# design.net
KiCad netlist of a schematic drawn in Altium Designer
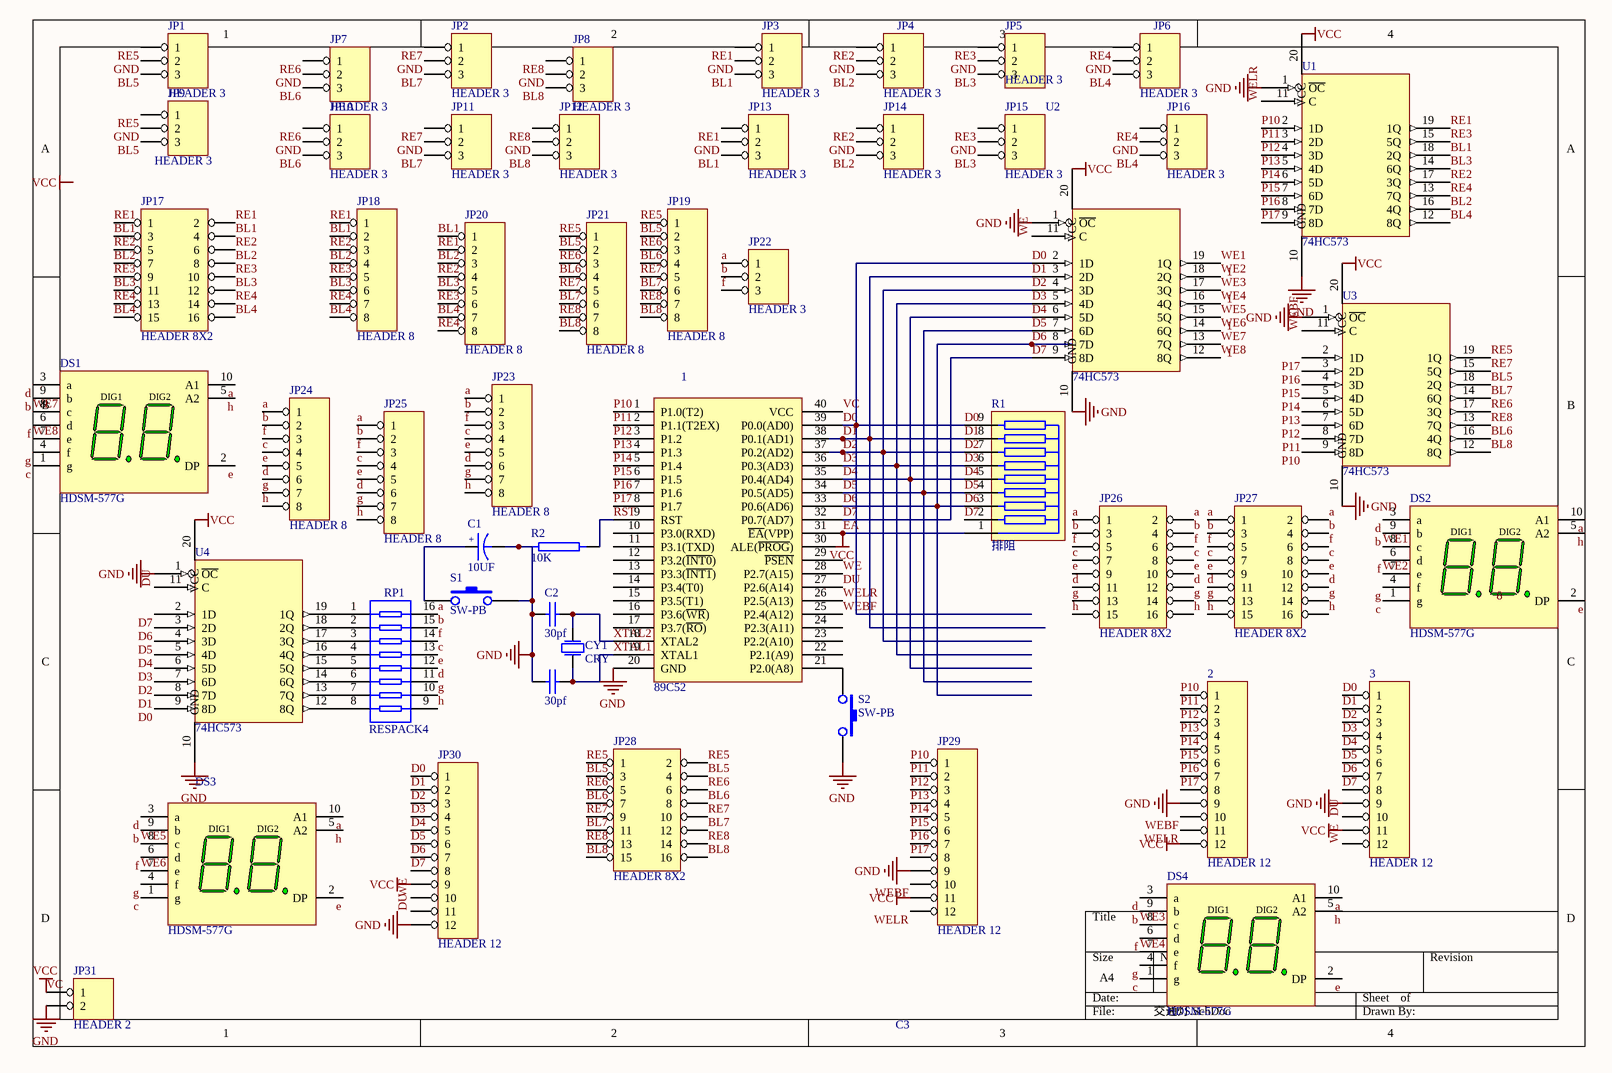
[diagram p0: 交通灯.SchDoc]

(export (version "E")
  (design (tool "Eeschema 10.0.6"))
  (components
    (comp (ref "1") (value "89C52") (footprint "DIP-40") (libsource (lib "51单片机") (part "89C52")))
    (comp (ref "2")
      (value "HEADER 12")
      (footprint "HDR1X12")
      (description "12 Pin Header")
      (libsource (lib "杂元件库") (part "HEADER 12"))
    )
    (comp (ref "3")
      (value "HEADER 12")
      (footprint "HDR1X12")
      (description "12 Pin Header")
      (libsource (lib "杂元件库") (part "HEADER 12"))
    )
    (comp (ref "C1")
      (value "10UF")
      (footprint "3216C")
      (description "钽电容")
      (libsource (lib "常用器件") (part "CAP-T"))
    )
    (comp (ref "C2") (value "30pf") (footprint "RAD0.1") (libsource (lib "C电容") (part "CAP1")))
    (comp (ref "C3") (value "30pf") (footprint "RAD0.1") (libsource (lib "C电容") (part "CAP1")))
    (comp (ref "CY1") (value "CRY") (footprint "XTAL-1") (libsource (lib "CRY晶振") (part "CRY")))
    (comp (ref "DS1")
      (value "HDSM-577G")
      (footprint "HDSM-577")
      (description "9.2 mm Green 7-Segment Display: 2-Digit, RH DP")
      (fields (field (name "PUBLISHER") "Altium Limited"))
      (libsource (lib "Avago LED Display 7-Segment, 2-Digit") (part "HDSM-577G"))
    )
    (comp (ref "DS2")
      (value "HDSM-577G")
      (footprint "HDSM-577")
      (description "9.2 mm Green 7-Segment Display: 2-Digit, RH DP")
      (fields (field (name "PUBLISHER") "Altium Limited"))
      (libsource (lib "Avago LED Display 7-Segment, 2-Digit") (part "HDSM-577G"))
    )
    (comp (ref "DS3")
      (value "HDSM-577G")
      (footprint "HDSM-577")
      (description "9.2 mm Green 7-Segment Display: 2-Digit, RH DP")
      (fields (field (name "PUBLISHER") "Altium Limited"))
      (libsource (lib "Avago LED Display 7-Segment, 2-Digit") (part "HDSM-577G"))
    )
    (comp (ref "DS4")
      (value "HDSM-577G")
      (footprint "HDSM-577")
      (description "9.2 mm Green 7-Segment Display: 2-Digit, RH DP")
      (fields (field (name "PUBLISHER") "Altium Limited"))
      (libsource (lib "Avago LED Display 7-Segment, 2-Digit") (part "HDSM-577G"))
    )
    (comp (ref "JP1")
      (value "HEADER 3")
      (footprint "Header3 80mil")
      (libsource (lib "杂元件库") (part "HEADER 3"))
    )
    (comp (ref "JP2")
      (value "HEADER 3")
      (footprint "Header3 80mil")
      (libsource (lib "杂元件库") (part "HEADER 3"))
    )
    (comp (ref "JP3")
      (value "HEADER 3")
      (footprint "Header3 80mil")
      (libsource (lib "杂元件库") (part "HEADER 3"))
    )
    (comp (ref "JP4")
      (value "HEADER 3")
      (footprint "Header3 80mil")
      (libsource (lib "杂元件库") (part "HEADER 3"))
    )
    (comp (ref "JP5")
      (value "HEADER 3")
      (footprint "Header3 80mil")
      (libsource (lib "杂元件库") (part "HEADER 3"))
    )
    (comp (ref "JP6")
      (value "HEADER 3")
      (footprint "Header3 80mil")
      (libsource (lib "杂元件库") (part "HEADER 3"))
    )
    (comp (ref "JP7")
      (value "HEADER 3")
      (footprint "Header3 80mil")
      (libsource (lib "杂元件库") (part "HEADER 3"))
    )
    (comp (ref "JP8")
      (value "HEADER 3")
      (footprint "Header3 80mil")
      (libsource (lib "杂元件库") (part "HEADER 3"))
    )
    (comp (ref "JP9")
      (value "HEADER 3")
      (footprint "Header3 80mil")
      (libsource (lib "杂元件库") (part "HEADER 3"))
    )
    (comp (ref "JP10")
      (value "HEADER 3")
      (footprint "Header3 80mil")
      (libsource (lib "杂元件库") (part "HEADER 3"))
    )
    (comp (ref "JP11")
      (value "HEADER 3")
      (footprint "Header3 80mil")
      (libsource (lib "杂元件库") (part "HEADER 3"))
    )
    (comp (ref "JP12")
      (value "HEADER 3")
      (footprint "Header3 80mil")
      (libsource (lib "杂元件库") (part "HEADER 3"))
    )
    (comp (ref "JP13")
      (value "HEADER 3")
      (footprint "Header3 80mil")
      (libsource (lib "杂元件库") (part "HEADER 3"))
    )
    (comp (ref "JP14")
      (value "HEADER 3")
      (footprint "Header3 80mil")
      (libsource (lib "杂元件库") (part "HEADER 3"))
    )
    (comp (ref "JP15")
      (value "HEADER 3")
      (footprint "Header3 80mil")
      (libsource (lib "杂元件库") (part "HEADER 3"))
    )
    (comp (ref "JP16")
      (value "HEADER 3")
      (footprint "Header3 80mil")
      (libsource (lib "杂元件库") (part "HEADER 3"))
    )
    (comp (ref "JP17") (value "HEADER 8X2") (footprint "HDR2X8") (libsource (lib "杂元件库") (part "HEADER 8X2")))
    (comp (ref "JP18")
      (value "HEADER 8")
      (footprint "HDR1X8")
      (description "8 Pin Header")
      (libsource (lib "杂元件库") (part "HEADER 8"))
    )
    (comp (ref "JP19")
      (value "HEADER 8")
      (footprint "HDR1X8")
      (description "8 Pin Header")
      (libsource (lib "杂元件库") (part "HEADER 8"))
    )
    (comp (ref "JP20")
      (value "HEADER 8")
      (footprint "HDR1X8")
      (description "8 Pin Header")
      (libsource (lib "杂元件库") (part "HEADER 8"))
    )
    (comp (ref "JP21")
      (value "HEADER 8")
      (footprint "HDR1X8")
      (description "8 Pin Header")
      (libsource (lib "杂元件库") (part "HEADER 8"))
    )
    (comp (ref "JP22")
      (value "HEADER 3")
      (footprint "Header3 80mil")
      (libsource (lib "杂元件库") (part "HEADER 3"))
    )
    (comp (ref "JP23")
      (value "HEADER 8")
      (footprint "HDR1X8")
      (description "8 Pin Header")
      (libsource (lib "杂元件库") (part "HEADER 8"))
    )
    (comp (ref "JP24")
      (value "HEADER 8")
      (footprint "HDR1X8")
      (description "8 Pin Header")
      (libsource (lib "杂元件库") (part "HEADER 8"))
    )
    (comp (ref "JP25")
      (value "HEADER 8")
      (footprint "HDR1X8")
      (description "8 Pin Header")
      (libsource (lib "杂元件库") (part "HEADER 8"))
    )
    (comp (ref "JP26") (value "HEADER 8X2") (footprint "HDR2X8") (libsource (lib "杂元件库") (part "HEADER 8X2")))
    (comp (ref "JP27") (value "HEADER 8X2") (footprint "HDR2X8") (libsource (lib "杂元件库") (part "HEADER 8X2")))
    (comp (ref "JP28") (value "HEADER 8X2") (footprint "HDR2X8") (libsource (lib "杂元件库") (part "HEADER 8X2")))
    (comp (ref "JP29")
      (value "HEADER 12")
      (footprint "HDR1X12")
      (description "12 Pin Header")
      (libsource (lib "杂元件库") (part "HEADER 12"))
    )
    (comp (ref "JP30")
      (value "HEADER 12")
      (footprint "HDR1X12")
      (description "12 Pin Header")
      (libsource (lib "杂元件库") (part "HEADER 12"))
    )
    (comp (ref "JP31") (value "HEADER 2") (footprint "HDR1X2") (libsource (lib "杂元件库") (part "HEADER 2")))
    (comp (ref "R1") (value "排阻") (footprint "sip9") (libsource (lib "R电阻") (part "排阻")))
    (comp (ref "R2") (value "10K") (footprint "AXIAL0.5") (libsource (lib "电阻(1)") (part "RES")))
    (comp (ref "RP1") (value "RESPACK4") (footprint "DIP16") (libsource (lib "电阻") (part "RESPACK4")))
    (comp (ref "S1") (value "SW-PB") (footprint "SWITCH") (libsource (lib "SW开关") (part "SW-PB")))
    (comp (ref "S2") (value "SW-PB") (footprint "SWITCH") (libsource (lib "SW开关") (part "SW-PB")))
    (comp (ref "U1") (value "74HC573") (footprint "DIP-20") (libsource (lib "74xxTTL") (part "74HC573")))
    (comp (ref "U2") (value "74HC573") (footprint "DIP-20") (libsource (lib "") (part "74HC573_1")))
    (comp (ref "U3") (value "74HC573") (footprint "DIP-20") (libsource (lib "74xxTTL") (part "74HC573")))
    (comp (ref "U4") (value "74HC573") (footprint "DIP-20") (libsource (lib "") (part "74HC573_1")))
  )
  (nets
    (net (code "3") (name "/BL1") (class "Default")
      (node (ref "JP13") (pin "3") (pinfunction "3_3") (pintype "passive"))
      (node (ref "JP17") (pin "3") (pinfunction "3_3") (pintype "passive"))
      (node (ref "JP17") (pin "4") (pinfunction "4_4") (pintype "passive"))
      (node (ref "JP18") (pin "2") (pinfunction "2_2") (pintype "passive"))
      (node (ref "JP20") (pin "1") (pinfunction "1_1") (pintype "passive"))
      (node (ref "JP3") (pin "3") (pinfunction "3_3") (pintype "passive"))
      (node (ref "U1") (pin "18") (pinfunction "2Q_18") (pintype "output"))
    )
    (net (code "4") (name "/BL2") (class "Default")
      (node (ref "JP14") (pin "3") (pinfunction "3_3") (pintype "passive"))
      (node (ref "JP17") (pin "7") (pinfunction "7_7") (pintype "passive"))
      (node (ref "JP17") (pin "8") (pinfunction "8_8") (pintype "passive"))
      (node (ref "JP18") (pin "4") (pinfunction "4_4") (pintype "passive"))
      (node (ref "JP20") (pin "3") (pinfunction "3_3") (pintype "passive"))
      (node (ref "JP4") (pin "3") (pinfunction "3_3") (pintype "passive"))
      (node (ref "U1") (pin "16") (pinfunction "4Q_16") (pintype "output"))
    )
    (net (code "5") (name "/BL3") (class "Default")
      (node (ref "JP15") (pin "3") (pinfunction "3_3") (pintype "passive"))
      (node (ref "JP17") (pin "11") (pinfunction "11_11") (pintype "passive"))
      (node (ref "JP17") (pin "12") (pinfunction "12_12") (pintype "passive"))
      (node (ref "JP18") (pin "6") (pinfunction "6_6") (pintype "passive"))
      (node (ref "JP20") (pin "5") (pinfunction "5_5") (pintype "passive"))
      (node (ref "JP5") (pin "3") (pinfunction "3_3") (pintype "passive"))
      (node (ref "U1") (pin "14") (pinfunction "6Q_14") (pintype "output"))
    )
    (net (code "6") (name "/BL4") (class "Default")
      (node (ref "JP16") (pin "3") (pinfunction "3_3") (pintype "passive"))
      (node (ref "JP17") (pin "15") (pinfunction "15_15") (pintype "passive"))
      (node (ref "JP17") (pin "16") (pinfunction "16_16") (pintype "passive"))
      (node (ref "JP18") (pin "8") (pinfunction "8_8") (pintype "passive"))
      (node (ref "JP20") (pin "7") (pinfunction "7_7") (pintype "passive"))
      (node (ref "JP6") (pin "3") (pinfunction "3_3") (pintype "passive"))
      (node (ref "U1") (pin "12") (pinfunction "8Q_12") (pintype "output"))
    )
    (net (code "7") (name "/BL5") (class "Default")
      (node (ref "JP1") (pin "3") (pinfunction "3_3") (pintype "passive"))
      (node (ref "JP19") (pin "2") (pinfunction "2_2") (pintype "passive"))
      (node (ref "JP21") (pin "2") (pinfunction "2_2") (pintype "passive"))
      (node (ref "JP28") (pin "3") (pinfunction "3_3") (pintype "passive"))
      (node (ref "JP28") (pin "4") (pinfunction "4_4") (pintype "passive"))
      (node (ref "JP9") (pin "3") (pinfunction "3_3") (pintype "passive"))
      (node (ref "U3") (pin "18") (pinfunction "2Q_18") (pintype "output"))
    )
    (net (code "8") (name "/BL6") (class "Default")
      (node (ref "JP10") (pin "3") (pinfunction "3_3") (pintype "passive"))
      (node (ref "JP19") (pin "4") (pinfunction "4_4") (pintype "passive"))
      (node (ref "JP21") (pin "4") (pinfunction "4_4") (pintype "passive"))
      (node (ref "JP28") (pin "7") (pinfunction "7_7") (pintype "passive"))
      (node (ref "JP28") (pin "8") (pinfunction "8_8") (pintype "passive"))
      (node (ref "JP7") (pin "3") (pinfunction "3_3") (pintype "passive"))
      (node (ref "U3") (pin "16") (pinfunction "4Q_16") (pintype "output"))
    )
    (net (code "9") (name "/BL7") (class "Default")
      (node (ref "JP11") (pin "3") (pinfunction "3_3") (pintype "passive"))
      (node (ref "JP19") (pin "6") (pinfunction "6_6") (pintype "passive"))
      (node (ref "JP2") (pin "3") (pinfunction "3_3") (pintype "passive"))
      (node (ref "JP21") (pin "6") (pinfunction "6_6") (pintype "passive"))
      (node (ref "JP28") (pin "11") (pinfunction "11_11") (pintype "passive"))
      (node (ref "JP28") (pin "12") (pinfunction "12_12") (pintype "passive"))
      (node (ref "U3") (pin "14") (pinfunction "6Q_14") (pintype "output"))
    )
    (net (code "10") (name "/BL8") (class "Default")
      (node (ref "JP12") (pin "3") (pinfunction "3_3") (pintype "passive"))
      (node (ref "JP19") (pin "8") (pinfunction "8_8") (pintype "passive"))
      (node (ref "JP21") (pin "8") (pinfunction "8_8") (pintype "passive"))
      (node (ref "JP28") (pin "15") (pinfunction "15_15") (pintype "passive"))
      (node (ref "JP28") (pin "16") (pinfunction "16_16") (pintype "passive"))
      (node (ref "JP8") (pin "3") (pinfunction "3_3") (pintype "passive"))
      (node (ref "U3") (pin "12") (pinfunction "8Q_12") (pintype "output"))
    )
    (net (code "11") (name "/D0") (class "Default")
      (node (ref "1") (pin "39") (pinfunction "P0.0(AD0)_39") (pintype "passive"))
      (node (ref "3") (pin "1") (pinfunction "1_1") (pintype "passive"))
      (node (ref "JP30") (pin "1") (pinfunction "1_1") (pintype "passive"))
      (node (ref "R1") (pin "9") (pinfunction "9_9") (pintype "passive"))
      (node (ref "U2") (pin "2") (pinfunction "1D_2") (pintype "input"))
      (node (ref "U4") (pin "9") (pinfunction "8D_9") (pintype "input"))
    )
    (net (code "12") (name "/D1") (class "Default")
      (node (ref "1") (pin "38") (pinfunction "P0.1(AD1)_38") (pintype "passive"))
      (node (ref "3") (pin "2") (pinfunction "2_2") (pintype "passive"))
      (node (ref "JP30") (pin "2") (pinfunction "2_2") (pintype "passive"))
      (node (ref "R1") (pin "8") (pinfunction "8_8") (pintype "passive"))
      (node (ref "U2") (pin "3") (pinfunction "2D_3") (pintype "input"))
      (node (ref "U4") (pin "8") (pinfunction "7D_8") (pintype "input"))
    )
    (net (code "13") (name "/D2") (class "Default")
      (node (ref "1") (pin "37") (pinfunction "P0.2(AD2)_37") (pintype "passive"))
      (node (ref "3") (pin "3") (pinfunction "3_3") (pintype "passive"))
      (node (ref "JP30") (pin "3") (pinfunction "3_3") (pintype "passive"))
      (node (ref "R1") (pin "7") (pinfunction "7_7") (pintype "passive"))
      (node (ref "U2") (pin "4") (pinfunction "3D_4") (pintype "input"))
      (node (ref "U4") (pin "7") (pinfunction "6D_7") (pintype "input"))
    )
    (net (code "14") (name "/D3") (class "Default")
      (node (ref "1") (pin "36") (pinfunction "P0.3(AD3)_36") (pintype "passive"))
      (node (ref "3") (pin "4") (pinfunction "4_4") (pintype "passive"))
      (node (ref "JP30") (pin "4") (pinfunction "4_4") (pintype "passive"))
      (node (ref "R1") (pin "6") (pinfunction "6_6") (pintype "passive"))
      (node (ref "U2") (pin "5") (pinfunction "4D_5") (pintype "input"))
      (node (ref "U4") (pin "6") (pinfunction "5D_6") (pintype "input"))
    )
    (net (code "15") (name "/D4") (class "Default")
      (node (ref "1") (pin "35") (pinfunction "P0.4(AD4)_35") (pintype "passive"))
      (node (ref "3") (pin "5") (pinfunction "5_5") (pintype "passive"))
      (node (ref "JP30") (pin "5") (pinfunction "5_5") (pintype "passive"))
      (node (ref "R1") (pin "5") (pinfunction "5_5") (pintype "passive"))
      (node (ref "U2") (pin "6") (pinfunction "5D_6") (pintype "input"))
      (node (ref "U4") (pin "5") (pinfunction "4D_5") (pintype "input"))
    )
    (net (code "16") (name "/D5") (class "Default")
      (node (ref "1") (pin "34") (pinfunction "P0.5(AD5)_34") (pintype "passive"))
      (node (ref "3") (pin "6") (pinfunction "6_6") (pintype "passive"))
      (node (ref "JP30") (pin "6") (pinfunction "6_6") (pintype "passive"))
      (node (ref "R1") (pin "4") (pinfunction "4_4") (pintype "passive"))
      (node (ref "U2") (pin "7") (pinfunction "6D_7") (pintype "input"))
      (node (ref "U4") (pin "4") (pinfunction "3D_4") (pintype "input"))
    )
    (net (code "17") (name "/D6") (class "Default")
      (node (ref "1") (pin "33") (pinfunction "P0.6(AD6)_33") (pintype "passive"))
      (node (ref "3") (pin "7") (pinfunction "7_7") (pintype "passive"))
      (node (ref "JP30") (pin "7") (pinfunction "7_7") (pintype "passive"))
      (node (ref "R1") (pin "3") (pinfunction "3_3") (pintype "passive"))
      (node (ref "U2") (pin "8") (pinfunction "7D_8") (pintype "input"))
      (node (ref "U4") (pin "3") (pinfunction "2D_3") (pintype "input"))
    )
    (net (code "18") (name "/D7") (class "Default")
      (node (ref "1") (pin "32") (pinfunction "P0.7(AD7)_32") (pintype "passive"))
      (node (ref "3") (pin "8") (pinfunction "8_8") (pintype "passive"))
      (node (ref "JP30") (pin "8") (pinfunction "8_8") (pintype "passive"))
      (node (ref "R1") (pin "2") (pinfunction "2_2") (pintype "passive"))
      (node (ref "U2") (pin "9") (pinfunction "8D_9") (pintype "input"))
      (node (ref "U4") (pin "2") (pinfunction "1D_2") (pintype "input"))
    )
    (net (code "19") (name "/DU") (class "Default")
      (node (ref "1") (pin "27") (pinfunction "P2.6(A14)_27") (pintype "passive"))
      (node (ref "3") (pin "10") (pinfunction "10_10") (pintype "passive"))
      (node (ref "JP30") (pin "11") (pinfunction "11_11") (pintype "passive"))
      (node (ref "U4") (pin "11") (pinfunction "C_11") (pintype "input"))
    )
    (net (code "20") (name "/P10") (class "Default")
      (node (ref "1") (pin "1") (pinfunction "P1.0(T2)_1") (pintype "passive"))
      (node (ref "2") (pin "1") (pinfunction "1_1") (pintype "passive"))
      (node (ref "JP29") (pin "1") (pinfunction "1_1") (pintype "passive"))
      (node (ref "U1") (pin "2") (pinfunction "1D_2") (pintype "input"))
      (node (ref "U3") (pin "9") (pinfunction "8D_9") (pintype "input"))
    )
    (net (code "21") (name "/P11") (class "Default")
      (node (ref "1") (pin "2") (pinfunction "P1.1(T2EX)_2") (pintype "passive"))
      (node (ref "2") (pin "2") (pinfunction "2_2") (pintype "passive"))
      (node (ref "JP29") (pin "2") (pinfunction "2_2") (pintype "passive"))
      (node (ref "U1") (pin "3") (pinfunction "2D_3") (pintype "input"))
      (node (ref "U3") (pin "8") (pinfunction "7D_8") (pintype "input"))
    )
    (net (code "22") (name "/P12") (class "Default")
      (node (ref "1") (pin "3") (pinfunction "P1.2_3") (pintype "passive"))
      (node (ref "2") (pin "3") (pinfunction "3_3") (pintype "passive"))
      (node (ref "JP29") (pin "3") (pinfunction "3_3") (pintype "passive"))
      (node (ref "U1") (pin "4") (pinfunction "3D_4") (pintype "input"))
      (node (ref "U3") (pin "7") (pinfunction "6D_7") (pintype "input"))
    )
    (net (code "23") (name "/P13") (class "Default")
      (node (ref "1") (pin "4") (pinfunction "P1.3_4") (pintype "passive"))
      (node (ref "2") (pin "4") (pinfunction "4_4") (pintype "passive"))
      (node (ref "JP29") (pin "4") (pinfunction "4_4") (pintype "passive"))
      (node (ref "U1") (pin "5") (pinfunction "4D_5") (pintype "input"))
      (node (ref "U3") (pin "6") (pinfunction "5D_6") (pintype "input"))
    )
    (net (code "24") (name "/P14") (class "Default")
      (node (ref "1") (pin "5") (pinfunction "P1.4_5") (pintype "passive"))
      (node (ref "2") (pin "5") (pinfunction "5_5") (pintype "passive"))
      (node (ref "JP29") (pin "5") (pinfunction "5_5") (pintype "passive"))
      (node (ref "U1") (pin "6") (pinfunction "5D_6") (pintype "input"))
      (node (ref "U3") (pin "5") (pinfunction "4D_5") (pintype "input"))
    )
    (net (code "25") (name "/P15") (class "Default")
      (node (ref "1") (pin "6") (pinfunction "P1.5_6") (pintype "passive"))
      (node (ref "2") (pin "6") (pinfunction "6_6") (pintype "passive"))
      (node (ref "JP29") (pin "6") (pinfunction "6_6") (pintype "passive"))
      (node (ref "U1") (pin "7") (pinfunction "6D_7") (pintype "input"))
      (node (ref "U3") (pin "4") (pinfunction "3D_4") (pintype "input"))
    )
    (net (code "26") (name "/P16") (class "Default")
      (node (ref "1") (pin "7") (pinfunction "P1.6_7") (pintype "passive"))
      (node (ref "2") (pin "7") (pinfunction "7_7") (pintype "passive"))
      (node (ref "JP29") (pin "7") (pinfunction "7_7") (pintype "passive"))
      (node (ref "U1") (pin "8") (pinfunction "7D_8") (pintype "input"))
      (node (ref "U3") (pin "3") (pinfunction "2D_3") (pintype "input"))
    )
    (net (code "27") (name "/P17") (class "Default")
      (node (ref "1") (pin "8") (pinfunction "P1.7_8") (pintype "passive"))
      (node (ref "2") (pin "8") (pinfunction "8_8") (pintype "passive"))
      (node (ref "JP29") (pin "8") (pinfunction "8_8") (pintype "passive"))
      (node (ref "U1") (pin "9") (pinfunction "8D_9") (pintype "input"))
      (node (ref "U3") (pin "2") (pinfunction "1D_2") (pintype "input"))
    )
    (net (code "28") (name "/RE1") (class "Default")
      (node (ref "JP13") (pin "1") (pinfunction "1_1") (pintype "passive"))
      (node (ref "JP17") (pin "1") (pinfunction "1_1") (pintype "passive"))
      (node (ref "JP17") (pin "2") (pinfunction "2_2") (pintype "passive"))
      (node (ref "JP18") (pin "1") (pinfunction "1_1") (pintype "passive"))
      (node (ref "JP20") (pin "2") (pinfunction "2_2") (pintype "passive"))
      (node (ref "JP3") (pin "1") (pinfunction "1_1") (pintype "passive"))
      (node (ref "U1") (pin "19") (pinfunction "1Q_19") (pintype "output"))
    )
    (net (code "29") (name "/RE2") (class "Default")
      (node (ref "JP14") (pin "1") (pinfunction "1_1") (pintype "passive"))
      (node (ref "JP17") (pin "5") (pinfunction "5_5") (pintype "passive"))
      (node (ref "JP17") (pin "6") (pinfunction "6_6") (pintype "passive"))
      (node (ref "JP18") (pin "3") (pinfunction "3_3") (pintype "passive"))
      (node (ref "JP20") (pin "4") (pinfunction "4_4") (pintype "passive"))
      (node (ref "JP4") (pin "1") (pinfunction "1_1") (pintype "passive"))
      (node (ref "U1") (pin "17") (pinfunction "3Q_17") (pintype "output"))
    )
    (net (code "30") (name "/RE3") (class "Default")
      (node (ref "JP15") (pin "1") (pinfunction "1_1") (pintype "passive"))
      (node (ref "JP17") (pin "10") (pinfunction "10_10") (pintype "passive"))
      (node (ref "JP17") (pin "9") (pinfunction "9_9") (pintype "passive"))
      (node (ref "JP18") (pin "5") (pinfunction "5_5") (pintype "passive"))
      (node (ref "JP20") (pin "6") (pinfunction "6_6") (pintype "passive"))
      (node (ref "JP5") (pin "1") (pinfunction "1_1") (pintype "passive"))
      (node (ref "U1") (pin "15") (pinfunction "5Q_15") (pintype "output"))
    )
    (net (code "31") (name "/RE4") (class "Default")
      (node (ref "JP16") (pin "1") (pinfunction "1_1") (pintype "passive"))
      (node (ref "JP17") (pin "13") (pinfunction "13_13") (pintype "passive"))
      (node (ref "JP17") (pin "14") (pinfunction "14_14") (pintype "passive"))
      (node (ref "JP18") (pin "7") (pinfunction "7_7") (pintype "passive"))
      (node (ref "JP20") (pin "8") (pinfunction "8_8") (pintype "passive"))
      (node (ref "JP6") (pin "1") (pinfunction "1_1") (pintype "passive"))
      (node (ref "U1") (pin "13") (pinfunction "7Q_13") (pintype "output"))
    )
    (net (code "32") (name "/RE5") (class "Default")
      (node (ref "JP1") (pin "1") (pinfunction "1_1") (pintype "passive"))
      (node (ref "JP19") (pin "1") (pinfunction "1_1") (pintype "passive"))
      (node (ref "JP21") (pin "1") (pinfunction "1_1") (pintype "passive"))
      (node (ref "JP28") (pin "1") (pinfunction "1_1") (pintype "passive"))
      (node (ref "JP28") (pin "2") (pinfunction "2_2") (pintype "passive"))
      (node (ref "JP9") (pin "1") (pinfunction "1_1") (pintype "passive"))
      (node (ref "U3") (pin "19") (pinfunction "1Q_19") (pintype "output"))
    )
    (net (code "33") (name "/RE6") (class "Default")
      (node (ref "JP10") (pin "1") (pinfunction "1_1") (pintype "passive"))
      (node (ref "JP19") (pin "3") (pinfunction "3_3") (pintype "passive"))
      (node (ref "JP21") (pin "3") (pinfunction "3_3") (pintype "passive"))
      (node (ref "JP28") (pin "5") (pinfunction "5_5") (pintype "passive"))
      (node (ref "JP28") (pin "6") (pinfunction "6_6") (pintype "passive"))
      (node (ref "JP7") (pin "1") (pinfunction "1_1") (pintype "passive"))
      (node (ref "U3") (pin "17") (pinfunction "3Q_17") (pintype "output"))
    )
    (net (code "34") (name "/RE7") (class "Default")
      (node (ref "JP11") (pin "1") (pinfunction "1_1") (pintype "passive"))
      (node (ref "JP19") (pin "5") (pinfunction "5_5") (pintype "passive"))
      (node (ref "JP2") (pin "1") (pinfunction "1_1") (pintype "passive"))
      (node (ref "JP21") (pin "5") (pinfunction "5_5") (pintype "passive"))
      (node (ref "JP28") (pin "10") (pinfunction "10_10") (pintype "passive"))
      (node (ref "JP28") (pin "9") (pinfunction "9_9") (pintype "passive"))
      (node (ref "U3") (pin "15") (pinfunction "5Q_15") (pintype "output"))
    )
    (net (code "35") (name "/RE8") (class "Default")
      (node (ref "JP12") (pin "1") (pinfunction "1_1") (pintype "passive"))
      (node (ref "JP19") (pin "7") (pinfunction "7_7") (pintype "passive"))
      (node (ref "JP21") (pin "7") (pinfunction "7_7") (pintype "passive"))
      (node (ref "JP28") (pin "13") (pinfunction "13_13") (pintype "passive"))
      (node (ref "JP28") (pin "14") (pinfunction "14_14") (pintype "passive"))
      (node (ref "JP8") (pin "1") (pinfunction "1_1") (pintype "passive"))
      (node (ref "U3") (pin "13") (pinfunction "7Q_13") (pintype "output"))
    )
    (net (code "36") (name "/RST") (class "Default")
      (node (ref "1") (pin "9") (pinfunction "RST_9") (pintype "passive"))
      (node (ref "R2") (pin "2") (pinfunction "2_2") (pintype "passive"))
    )
    (net (code "37") (name "/WE") (class "Default")
      (node (ref "1") (pin "28") (pinfunction "P2.7(A15)_28") (pintype "passive"))
      (node (ref "3") (pin "12") (pinfunction "12_12") (pintype "passive"))
      (node (ref "JP30") (pin "10") (pinfunction "10_10") (pintype "passive"))
      (node (ref "U2") (pin "11") (pinfunction "C_11") (pintype "input"))
    )
    (net (code "38") (name "/WE1") (class "Default")
      (node (ref "DS2") (pin "8") (pinfunction "c_8") (pintype "passive"))
      (node (ref "U2") (pin "19") (pinfunction "1Q_19") (pintype "output"))
    )
    (net (code "39") (name "/WE2") (class "Default")
      (node (ref "DS2") (pin "7") (pinfunction "e_7") (pintype "passive"))
      (node (ref "U2") (pin "18") (pinfunction "2Q_18") (pintype "output"))
    )
    (net (code "40") (name "/WE3") (class "Default")
      (node (ref "DS4") (pin "8") (pinfunction "c_8") (pintype "passive"))
      (node (ref "U2") (pin "17") (pinfunction "3Q_17") (pintype "output"))
    )
    (net (code "41") (name "/WE4") (class "Default")
      (node (ref "DS4") (pin "7") (pinfunction "e_7") (pintype "passive"))
      (node (ref "U2") (pin "16") (pinfunction "4Q_16") (pintype "output"))
    )
    (net (code "42") (name "/WE5") (class "Default")
      (node (ref "DS3") (pin "8") (pinfunction "c_8") (pintype "passive"))
      (node (ref "U2") (pin "15") (pinfunction "5Q_15") (pintype "output"))
    )
    (net (code "43") (name "/WE6") (class "Default")
      (node (ref "DS3") (pin "7") (pinfunction "e_7") (pintype "passive"))
      (node (ref "U2") (pin "14") (pinfunction "6Q_14") (pintype "output"))
    )
    (net (code "44") (name "/WE7") (class "Default")
      (node (ref "DS1") (pin "8") (pinfunction "c_8") (pintype "passive"))
      (node (ref "U2") (pin "13") (pinfunction "7Q_13") (pintype "output"))
    )
    (net (code "45") (name "/WE8") (class "Default")
      (node (ref "DS1") (pin "7") (pinfunction "e_7") (pintype "passive"))
      (node (ref "U2") (pin "12") (pinfunction "8Q_12") (pintype "output"))
    )
    (net (code "46") (name "/WEBF") (class "Default")
      (node (ref "1") (pin "25") (pinfunction "P2.4(A12)_25") (pintype "passive"))
      (node (ref "2") (pin "10") (pinfunction "10_10") (pintype "passive"))
      (node (ref "JP29") (pin "10") (pinfunction "10_10") (pintype "passive"))
      (node (ref "U3") (pin "11") (pinfunction "C_11") (pintype "input"))
    )
    (net (code "47") (name "/WELR") (class "Default")
      (node (ref "1") (pin "26") (pinfunction "P2.5(A13)_26") (pintype "passive"))
      (node (ref "2") (pin "11") (pinfunction "11_11") (pintype "passive"))
      (node (ref "JP29") (pin "12") (pinfunction "12_12") (pintype "passive"))
      (node (ref "U1") (pin "11") (pinfunction "C_11") (pintype "input"))
    )
    (net (code "48") (name "/XTAL1") (class "Default")
      (node (ref "1") (pin "19") (pinfunction "XTAL1_19") (pintype "passive"))
      (node (ref "C3") (pin "1") (pinfunction "1_1") (pintype "passive"))
      (node (ref "CY1") (pin "2") (pinfunction "P2_2") (pintype "passive"))
    )
    (net (code "49") (name "/XTAL2") (class "Default")
      (node (ref "1") (pin "18") (pinfunction "XTAL2_18") (pintype "passive"))
      (node (ref "C2") (pin "1") (pinfunction "1_1") (pintype "passive"))
      (node (ref "CY1") (pin "1") (pinfunction "P1_1") (pintype "passive"))
    )
    (net (code "50") (name "/a") (class "Default")
      (node (ref "DS1") (pin "10") (pinfunction "A1_10") (pintype "passive"))
      (node (ref "DS2") (pin "10") (pinfunction "A1_10") (pintype "passive"))
      (node (ref "DS3") (pin "10") (pinfunction "A1_10") (pintype "passive"))
      (node (ref "DS4") (pin "10") (pinfunction "A1_10") (pintype "passive"))
      (node (ref "JP22") (pin "1") (pinfunction "1_1") (pintype "passive"))
      (node (ref "JP23") (pin "1") (pinfunction "1_1") (pintype "passive"))
      (node (ref "JP24") (pin "1") (pinfunction "1_1") (pintype "passive"))
      (node (ref "JP25") (pin "1") (pinfunction "1_1") (pintype "passive"))
      (node (ref "JP26") (pin "1") (pinfunction "1_1") (pintype "passive"))
      (node (ref "JP26") (pin "2") (pinfunction "2_2") (pintype "passive"))
      (node (ref "JP27") (pin "1") (pinfunction "1_1") (pintype "passive"))
      (node (ref "JP27") (pin "2") (pinfunction "2_2") (pintype "passive"))
      (node (ref "RP1") (pin "16") (pinfunction "16_16") (pintype "passive"))
    )
    (net (code "51") (name "/b") (class "Default")
      (node (ref "DS1") (pin "9") (pinfunction "b_9") (pintype "passive"))
      (node (ref "DS2") (pin "9") (pinfunction "b_9") (pintype "passive"))
      (node (ref "DS3") (pin "9") (pinfunction "b_9") (pintype "passive"))
      (node (ref "DS4") (pin "9") (pinfunction "b_9") (pintype "passive"))
      (node (ref "JP22") (pin "2") (pinfunction "2_2") (pintype "passive"))
      (node (ref "JP23") (pin "2") (pinfunction "2_2") (pintype "passive"))
      (node (ref "JP24") (pin "2") (pinfunction "2_2") (pintype "passive"))
      (node (ref "JP25") (pin "2") (pinfunction "2_2") (pintype "passive"))
      (node (ref "JP26") (pin "3") (pinfunction "3_3") (pintype "passive"))
      (node (ref "JP26") (pin "4") (pinfunction "4_4") (pintype "passive"))
      (node (ref "JP27") (pin "3") (pinfunction "3_3") (pintype "passive"))
      (node (ref "JP27") (pin "4") (pinfunction "4_4") (pintype "passive"))
      (node (ref "RP1") (pin "15") (pinfunction "15_15") (pintype "passive"))
    )
    (net (code "52") (name "/c") (class "Default")
      (node (ref "DS1") (pin "1") (pinfunction "g_1") (pintype "passive"))
      (node (ref "DS2") (pin "1") (pinfunction "g_1") (pintype "passive"))
      (node (ref "DS3") (pin "1") (pinfunction "g_1") (pintype "passive"))
      (node (ref "DS4") (pin "1") (pinfunction "g_1") (pintype "passive"))
      (node (ref "JP23") (pin "4") (pinfunction "4_4") (pintype "passive"))
      (node (ref "JP24") (pin "4") (pinfunction "4_4") (pintype "passive"))
      (node (ref "JP25") (pin "4") (pinfunction "4_4") (pintype "passive"))
      (node (ref "JP26") (pin "7") (pinfunction "7_7") (pintype "passive"))
      (node (ref "JP26") (pin "8") (pinfunction "8_8") (pintype "passive"))
      (node (ref "JP27") (pin "7") (pinfunction "7_7") (pintype "passive"))
      (node (ref "JP27") (pin "8") (pinfunction "8_8") (pintype "passive"))
      (node (ref "RP1") (pin "13") (pinfunction "13_13") (pintype "passive"))
    )
    (net (code "53") (name "/d") (class "Default")
      (node (ref "DS1") (pin "3") (pinfunction "a_3") (pintype "passive"))
      (node (ref "DS2") (pin "3") (pinfunction "a_3") (pintype "passive"))
      (node (ref "DS3") (pin "3") (pinfunction "a_3") (pintype "passive"))
      (node (ref "DS4") (pin "3") (pinfunction "a_3") (pintype "passive"))
      (node (ref "JP23") (pin "6") (pinfunction "6_6") (pintype "passive"))
      (node (ref "JP24") (pin "6") (pinfunction "6_6") (pintype "passive"))
      (node (ref "JP25") (pin "6") (pinfunction "6_6") (pintype "passive"))
      (node (ref "JP26") (pin "11") (pinfunction "11_11") (pintype "passive"))
      (node (ref "JP26") (pin "12") (pinfunction "12_12") (pintype "passive"))
      (node (ref "JP27") (pin "11") (pinfunction "11_11") (pintype "passive"))
      (node (ref "JP27") (pin "12") (pinfunction "12_12") (pintype "passive"))
      (node (ref "RP1") (pin "11") (pinfunction "11_11") (pintype "passive"))
    )
    (net (code "54") (name "/e") (class "Default")
      (node (ref "DS1") (pin "2") (pinfunction "DP_2") (pintype "passive"))
      (node (ref "DS2") (pin "2") (pinfunction "DP_2") (pintype "passive"))
      (node (ref "DS3") (pin "2") (pinfunction "DP_2") (pintype "passive"))
      (node (ref "DS4") (pin "2") (pinfunction "DP_2") (pintype "passive"))
      (node (ref "JP23") (pin "5") (pinfunction "5_5") (pintype "passive"))
      (node (ref "JP24") (pin "5") (pinfunction "5_5") (pintype "passive"))
      (node (ref "JP25") (pin "5") (pinfunction "5_5") (pintype "passive"))
      (node (ref "JP26") (pin "10") (pinfunction "10_10") (pintype "passive"))
      (node (ref "JP26") (pin "9") (pinfunction "9_9") (pintype "passive"))
      (node (ref "JP27") (pin "10") (pinfunction "10_10") (pintype "passive"))
      (node (ref "JP27") (pin "9") (pinfunction "9_9") (pintype "passive"))
      (node (ref "RP1") (pin "12") (pinfunction "12_12") (pintype "passive"))
    )
    (net (code "55") (name "/f") (class "Default")
      (node (ref "DS1") (pin "6") (pinfunction "d_6") (pintype "passive"))
      (node (ref "DS2") (pin "6") (pinfunction "d_6") (pintype "passive"))
      (node (ref "DS3") (pin "6") (pinfunction "d_6") (pintype "passive"))
      (node (ref "DS4") (pin "6") (pinfunction "d_6") (pintype "passive"))
      (node (ref "JP22") (pin "3") (pinfunction "3_3") (pintype "passive"))
      (node (ref "JP23") (pin "3") (pinfunction "3_3") (pintype "passive"))
      (node (ref "JP24") (pin "3") (pinfunction "3_3") (pintype "passive"))
      (node (ref "JP25") (pin "3") (pinfunction "3_3") (pintype "passive"))
      (node (ref "JP26") (pin "5") (pinfunction "5_5") (pintype "passive"))
      (node (ref "JP26") (pin "6") (pinfunction "6_6") (pintype "passive"))
      (node (ref "JP27") (pin "5") (pinfunction "5_5") (pintype "passive"))
      (node (ref "JP27") (pin "6") (pinfunction "6_6") (pintype "passive"))
      (node (ref "RP1") (pin "14") (pinfunction "14_14") (pintype "passive"))
    )
    (net (code "56") (name "/g") (class "Default")
      (node (ref "DS1") (pin "4") (pinfunction "f_4") (pintype "passive"))
      (node (ref "DS2") (pin "4") (pinfunction "f_4") (pintype "passive"))
      (node (ref "DS3") (pin "4") (pinfunction "f_4") (pintype "passive"))
      (node (ref "DS4") (pin "4") (pinfunction "f_4") (pintype "passive"))
      (node (ref "JP23") (pin "7") (pinfunction "7_7") (pintype "passive"))
      (node (ref "JP24") (pin "7") (pinfunction "7_7") (pintype "passive"))
      (node (ref "JP25") (pin "7") (pinfunction "7_7") (pintype "passive"))
      (node (ref "JP26") (pin "13") (pinfunction "13_13") (pintype "passive"))
      (node (ref "JP26") (pin "14") (pinfunction "14_14") (pintype "passive"))
      (node (ref "JP27") (pin "13") (pinfunction "13_13") (pintype "passive"))
      (node (ref "JP27") (pin "14") (pinfunction "14_14") (pintype "passive"))
      (node (ref "RP1") (pin "10") (pinfunction "10_10") (pintype "passive"))
    )
    (net (code "57") (name "/h") (class "Default")
      (node (ref "DS1") (pin "5") (pinfunction "A2_5") (pintype "passive"))
      (node (ref "DS2") (pin "5") (pinfunction "A2_5") (pintype "passive"))
      (node (ref "DS3") (pin "5") (pinfunction "A2_5") (pintype "passive"))
      (node (ref "DS4") (pin "5") (pinfunction "A2_5") (pintype "passive"))
      (node (ref "JP23") (pin "8") (pinfunction "8_8") (pintype "passive"))
      (node (ref "JP24") (pin "8") (pinfunction "8_8") (pintype "passive"))
      (node (ref "JP25") (pin "8") (pinfunction "8_8") (pintype "passive"))
      (node (ref "JP26") (pin "15") (pinfunction "15_15") (pintype "passive"))
      (node (ref "JP26") (pin "16") (pinfunction "16_16") (pintype "passive"))
      (node (ref "JP27") (pin "15") (pinfunction "15_15") (pintype "passive"))
      (node (ref "JP27") (pin "16") (pinfunction "16_16") (pintype "passive"))
      (node (ref "RP1") (pin "9") (pinfunction "9_9") (pintype "passive"))
    )
    (net (code "58") (name "GND") (class "Default")
      (node (ref "1") (pin "20") (pinfunction "GND_20") (pintype "passive"))
      (node (ref "2") (pin "9") (pinfunction "9_9") (pintype "passive"))
      (node (ref "3") (pin "9") (pinfunction "9_9") (pintype "passive"))
      (node (ref "C1") (pin "2") (pinfunction "2_2") (pintype "passive"))
      (node (ref "C2") (pin "2") (pinfunction "2_2") (pintype "passive"))
      (node (ref "C3") (pin "2") (pinfunction "2_2") (pintype "passive"))
      (node (ref "JP1") (pin "2") (pinfunction "2_2") (pintype "passive"))
      (node (ref "JP10") (pin "2") (pinfunction "2_2") (pintype "passive"))
      (node (ref "JP11") (pin "2") (pinfunction "2_2") (pintype "passive"))
      (node (ref "JP12") (pin "2") (pinfunction "2_2") (pintype "passive"))
      (node (ref "JP13") (pin "2") (pinfunction "2_2") (pintype "passive"))
      (node (ref "JP14") (pin "2") (pinfunction "2_2") (pintype "passive"))
      (node (ref "JP15") (pin "2") (pinfunction "2_2") (pintype "passive"))
      (node (ref "JP16") (pin "2") (pinfunction "2_2") (pintype "passive"))
      (node (ref "JP2") (pin "2") (pinfunction "2_2") (pintype "passive"))
      (node (ref "JP29") (pin "9") (pinfunction "9_9") (pintype "passive"))
      (node (ref "JP3") (pin "2") (pinfunction "2_2") (pintype "passive"))
      (node (ref "JP30") (pin "12") (pinfunction "12_12") (pintype "passive"))
      (node (ref "JP31") (pin "2") (pinfunction "2_2") (pintype "passive"))
      (node (ref "JP4") (pin "2") (pinfunction "2_2") (pintype "passive"))
      (node (ref "JP5") (pin "2") (pinfunction "2_2") (pintype "passive"))
      (node (ref "JP6") (pin "2") (pinfunction "2_2") (pintype "passive"))
      (node (ref "JP7") (pin "2") (pinfunction "2_2") (pintype "passive"))
      (node (ref "JP8") (pin "2") (pinfunction "2_2") (pintype "passive"))
      (node (ref "JP9") (pin "2") (pinfunction "2_2") (pintype "passive"))
      (node (ref "R2") (pin "1") (pinfunction "1_1") (pintype "passive"))
      (node (ref "S1") (pin "2") (pinfunction "2_2") (pintype "passive"))
      (node (ref "S2") (pin "2") (pinfunction "2_2") (pintype "passive"))
      (node (ref "U1") (pin "1") (pinfunction "~{OC}_1") (pintype "input"))
      (node (ref "U1") (pin "10") (pinfunction "GND_10") (pintype "power_in"))
      (node (ref "U2") (pin "1") (pinfunction "~{OC}_1") (pintype "input"))
      (node (ref "U2") (pin "10") (pinfunction "GND_10") (pintype "power_in"))
      (node (ref "U3") (pin "1") (pinfunction "~{OC}_1") (pintype "input"))
      (node (ref "U3") (pin "10") (pinfunction "GND_10") (pintype "power_in"))
      (node (ref "U4") (pin "1") (pinfunction "~{OC}_1") (pintype "input"))
      (node (ref "U4") (pin "10") (pinfunction "GND_10") (pintype "power_in"))
    )
    (net (code "59") (name "Net-(1-P2.0(A8))") (class "Default")
      (node (ref "1") (pin "21") (pinfunction "P2.0(A8)_21") (pintype "passive"))
      (node (ref "S2") (pin "1") (pinfunction "1_1") (pintype "passive"))
    )
    (net (code "60") (name "Net-(C1-Pad1)") (class "Default")
      (node (ref "C1") (pin "1") (pinfunction "1_1") (pintype "passive"))
      (node (ref "S1") (pin "1") (pinfunction "1_1") (pintype "passive"))
    )
    (net (code "61") (name "Net-(U4-1Q)") (class "Default")
      (node (ref "RP1") (pin "1") (pinfunction "1_1") (pintype "passive"))
      (node (ref "U4") (pin "19") (pinfunction "1Q_19") (pintype "output"))
    )
    (net (code "62") (name "Net-(U4-2Q)") (class "Default")
      (node (ref "RP1") (pin "2") (pinfunction "2_2") (pintype "passive"))
      (node (ref "U4") (pin "18") (pinfunction "2Q_18") (pintype "output"))
    )
    (net (code "63") (name "Net-(U4-3Q)") (class "Default")
      (node (ref "RP1") (pin "3") (pinfunction "3_3") (pintype "passive"))
      (node (ref "U4") (pin "17") (pinfunction "3Q_17") (pintype "output"))
    )
    (net (code "64") (name "Net-(U4-4Q)") (class "Default")
      (node (ref "RP1") (pin "4") (pinfunction "4_4") (pintype "passive"))
      (node (ref "U4") (pin "16") (pinfunction "4Q_16") (pintype "output"))
    )
    (net (code "65") (name "Net-(U4-5Q)") (class "Default")
      (node (ref "RP1") (pin "5") (pinfunction "5_5") (pintype "passive"))
      (node (ref "U4") (pin "15") (pinfunction "5Q_15") (pintype "output"))
    )
    (net (code "66") (name "Net-(U4-6Q)") (class "Default")
      (node (ref "RP1") (pin "6") (pinfunction "6_6") (pintype "passive"))
      (node (ref "U4") (pin "14") (pinfunction "6Q_14") (pintype "output"))
    )
    (net (code "67") (name "Net-(U4-7Q)") (class "Default")
      (node (ref "RP1") (pin "7") (pinfunction "7_7") (pintype "passive"))
      (node (ref "U4") (pin "13") (pinfunction "7Q_13") (pintype "output"))
    )
    (net (code "68") (name "Net-(U4-8Q)") (class "Default")
      (node (ref "RP1") (pin "8") (pinfunction "8_8") (pintype "passive"))
      (node (ref "U4") (pin "12") (pinfunction "8Q_12") (pintype "output"))
    )
    (net (code "69") (name "VCC") (class "Default")
      (node (ref "1") (pin "31") (pinfunction "~{EA}(VPP)_31") (pintype "passive"))
      (node (ref "1") (pin "40") (pinfunction "VCC_40") (pintype "passive"))
      (node (ref "2") (pin "12") (pinfunction "12_12") (pintype "passive"))
      (node (ref "3") (pin "11") (pinfunction "11_11") (pintype "passive"))
      (node (ref "JP29") (pin "11") (pinfunction "11_11") (pintype "passive"))
      (node (ref "JP30") (pin "9") (pinfunction "9_9") (pintype "passive"))
      (node (ref "JP31") (pin "1") (pinfunction "1_1") (pintype "passive"))
      (node (ref "R1") (pin "1") (pinfunction "1_1") (pintype "passive"))
      (node (ref "U1") (pin "20") (pinfunction "VCC_20") (pintype "power_in"))
      (node (ref "U2") (pin "20") (pinfunction "VCC_20") (pintype "power_in"))
      (node (ref "U3") (pin "20") (pinfunction "VCC_20") (pintype "power_in"))
      (node (ref "U4") (pin "20") (pinfunction "VCC_20") (pintype "power_in"))
    )
    (net (code "70") (name "unconnected-(1-ALE(~{PROG})-Pad30)") (class "Default")
      (node (ref "1") (pin "30") (pinfunction "ALE(~{PROG})_30") (pintype "passive"))
    )
    (net (code "71") (name "unconnected-(1-P2.1(A9)-Pad22)") (class "Default")
      (node (ref "1") (pin "22") (pinfunction "P2.1(A9)_22") (pintype "passive"))
    )
    (net (code "72") (name "unconnected-(1-P2.2(A10)-Pad23)") (class "Default")
      (node (ref "1") (pin "23") (pinfunction "P2.2(A10)_23") (pintype "passive"))
    )
    (net (code "73") (name "unconnected-(1-P2.3(A11)-Pad24)") (class "Default")
      (node (ref "1") (pin "24") (pinfunction "P2.3(A11)_24") (pintype "passive"))
    )
    (net (code "74") (name "unconnected-(1-P3.0(RXD)-Pad10)") (class "Default")
      (node (ref "1") (pin "10") (pinfunction "P3.0(RXD)_10") (pintype "passive"))
    )
    (net (code "75") (name "unconnected-(1-P3.1(TXD)-Pad11)") (class "Default")
      (node (ref "1") (pin "11") (pinfunction "P3.1(TXD)_11") (pintype "passive"))
    )
    (net (code "76") (name "unconnected-(1-P3.2(~{INT0})-Pad12)") (class "Default")
      (node (ref "1") (pin "12") (pinfunction "P3.2(~{INT0})_12") (pintype "passive"))
    )
    (net (code "77") (name "unconnected-(1-P3.3(~{INT1})-Pad13)") (class "Default")
      (node (ref "1") (pin "13") (pinfunction "P3.3(~{INT1})_13") (pintype "passive"))
    )
    (net (code "78") (name "unconnected-(1-P3.4(T0)-Pad14)") (class "Default")
      (node (ref "1") (pin "14") (pinfunction "P3.4(T0)_14") (pintype "passive"))
    )
    (net (code "79") (name "unconnected-(1-P3.5(T1)-Pad15)") (class "Default")
      (node (ref "1") (pin "15") (pinfunction "P3.5(T1)_15") (pintype "passive"))
    )
    (net (code "80") (name "unconnected-(1-P3.6(~{WR})-Pad16)") (class "Default")
      (node (ref "1") (pin "16") (pinfunction "P3.6(~{WR})_16") (pintype "passive"))
    )
    (net (code "81") (name "unconnected-(1-P3.7(~{RO})-Pad17)") (class "Default")
      (node (ref "1") (pin "17") (pinfunction "P3.7(~{RO})_17") (pintype "passive"))
    )
    (net (code "82") (name "unconnected-(1-~{PSEN}-Pad29)") (class "Default")
      (node (ref "1") (pin "29") (pinfunction "~{PSEN}_29") (pintype "passive"))
    )
  )
)
